# Qwiic_Mux_PCA9846.net
KiCad netlist of a schematic drawn in EAGLE
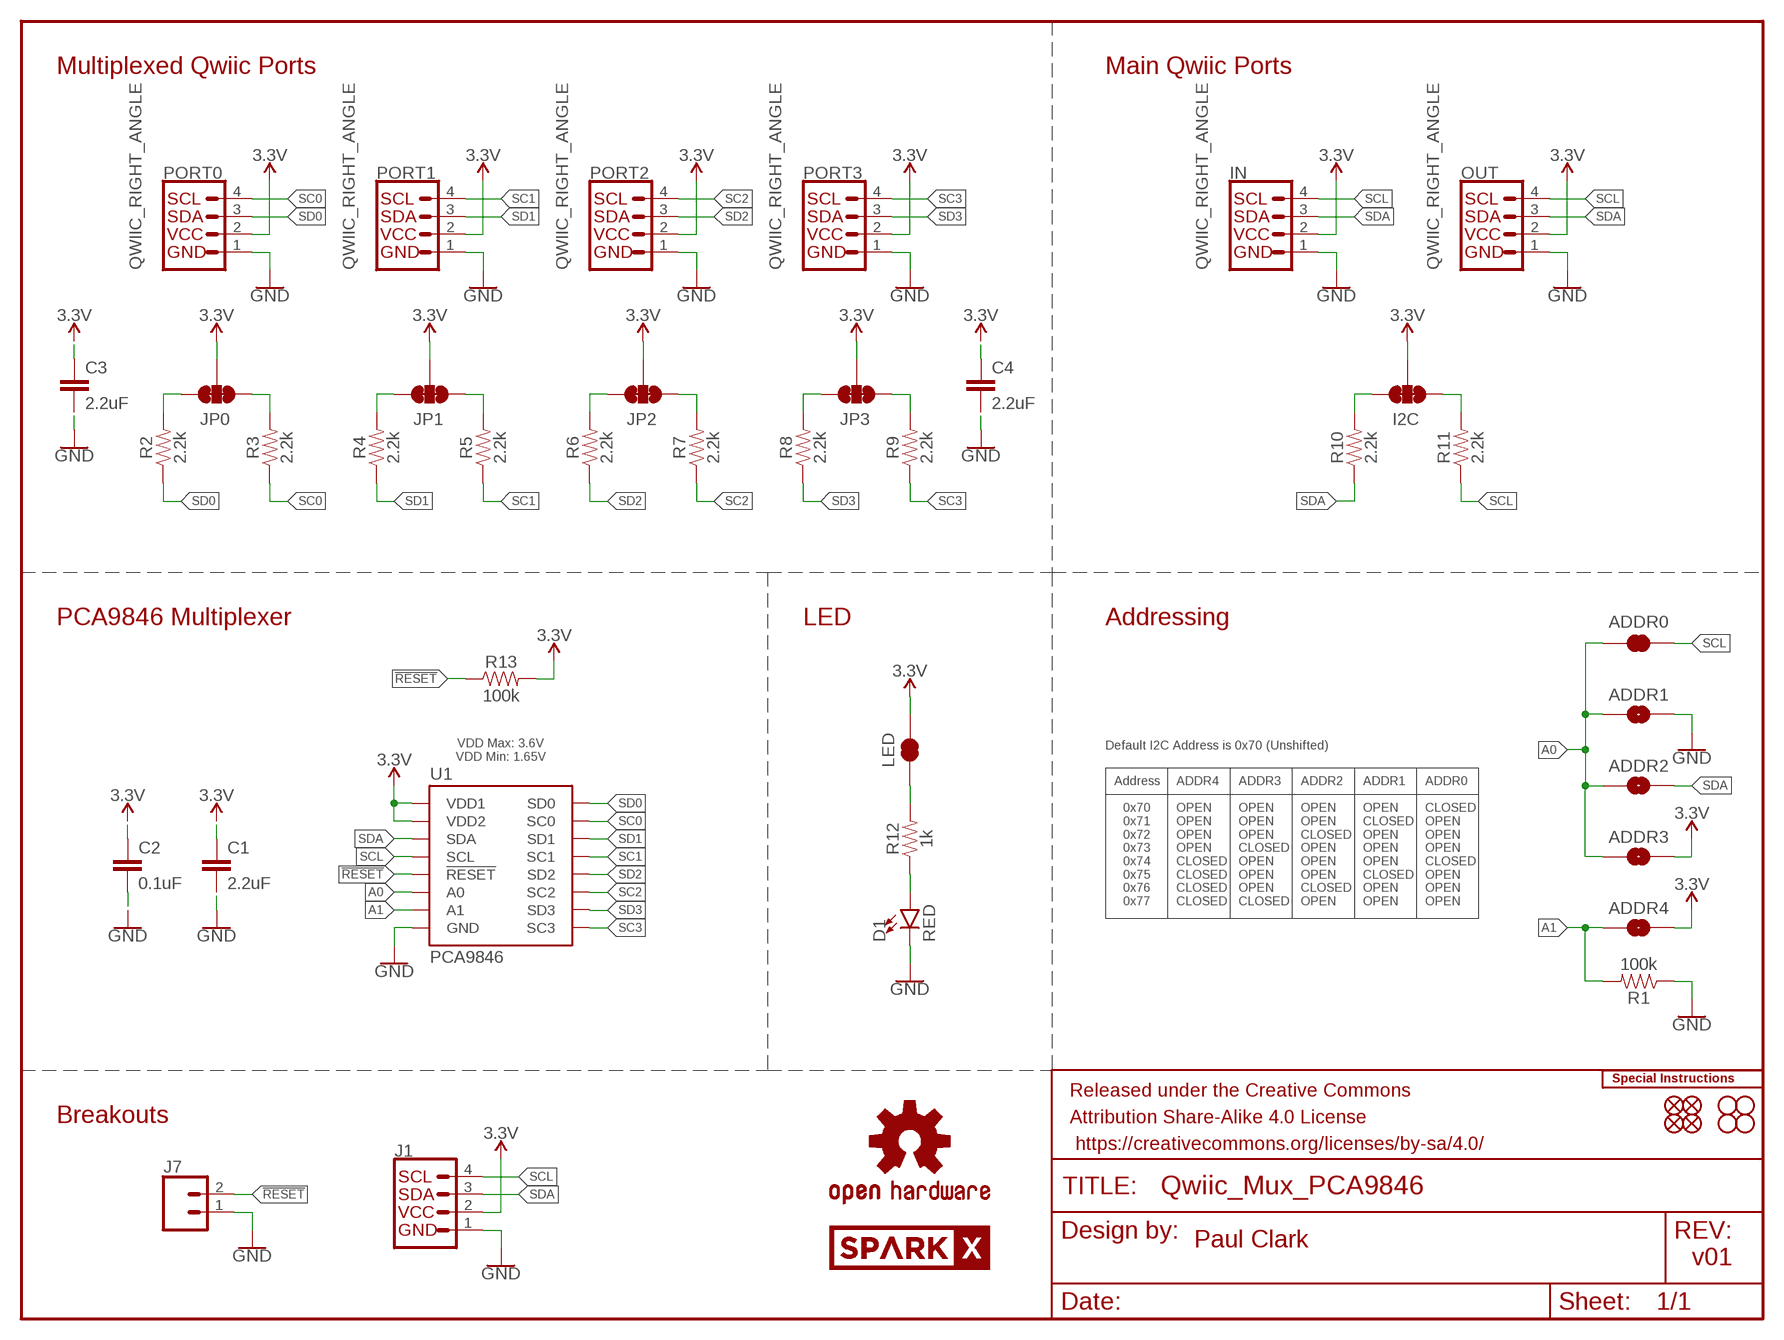
[diagram p0: schematic, sheet 1]

(export (version "E")
  (design (tool "Eeschema 10.0.6"))
  (components
    (comp (ref "ADDR0")
      (value "JUMPER-SMT_2_NC_TRACE_SILK")
      (footprint "eagle-import:SMT-JUMPER_2_NC_TRACE_SILK")
      (libsource (lib "eagle-import") (part "JUMPER-SMT_2_NC_TRACE_SILK"))
    )
    (comp (ref "ADDR1")
      (value "JUMPER-SMT_2_NO_SILK")
      (footprint "eagle-import:SMT-JUMPER_2_NO_SILK")
      (libsource (lib "eagle-import") (part "JUMPER-SMT_2_NO_SILK"))
    )
    (comp (ref "ADDR2")
      (value "JUMPER-SMT_2_NO_SILK")
      (footprint "eagle-import:SMT-JUMPER_2_NO_SILK")
      (libsource (lib "eagle-import") (part "JUMPER-SMT_2_NO_SILK"))
    )
    (comp (ref "ADDR3")
      (value "JUMPER-SMT_2_NO_SILK")
      (footprint "eagle-import:SMT-JUMPER_2_NO_SILK")
      (libsource (lib "eagle-import") (part "JUMPER-SMT_2_NO_SILK"))
    )
    (comp (ref "ADDR4")
      (value "JUMPER-SMT_2_NO_SILK")
      (footprint "eagle-import:SMT-JUMPER_2_NO_SILK")
      (libsource (lib "eagle-import") (part "JUMPER-SMT_2_NO_SILK"))
    )
    (comp (ref "C1")
      (value "2.2uF")
      (footprint "eagle-import:0402-TIGHT")
      (libsource (lib "eagle-import") (part "2.2UF-0402_TIGHT-10V-10%-X5R"))
    )
    (comp (ref "C2")
      (value "0.1uF")
      (footprint "eagle-import:0402-TIGHT")
      (libsource (lib "eagle-import") (part "0.1UF-0402T-6.3V-10%-X7R"))
    )
    (comp (ref "C3")
      (value "2.2uF")
      (footprint "eagle-import:0402-TIGHT")
      (libsource (lib "eagle-import") (part "2.2UF-0402_TIGHT-10V-10%-X5R"))
    )
    (comp (ref "C4")
      (value "2.2uF")
      (footprint "eagle-import:0402-TIGHT")
      (libsource (lib "eagle-import") (part "2.2UF-0402_TIGHT-10V-10%-X5R"))
    )
    (comp (ref "D1")
      (value "RED")
      (footprint "eagle-import:LED-0603")
      (libsource (lib "eagle-import") (part "LED-RED0603"))
    )
    (comp (ref "FD1")
      (value "FIDUCIAL1X2")
      (footprint "eagle-import:FIDUCIAL-1X2")
      (libsource (lib "eagle-import") (part "FIDUCIAL1X2"))
    )
    (comp (ref "FD2")
      (value "FIDUCIAL1X2")
      (footprint "eagle-import:FIDUCIAL-1X2")
      (libsource (lib "eagle-import") (part "FIDUCIAL1X2"))
    )
    (comp (ref "FD3")
      (value "FIDUCIAL1X2")
      (footprint "eagle-import:FIDUCIAL-1X2")
      (libsource (lib "eagle-import") (part "FIDUCIAL1X2"))
    )
    (comp (ref "FD4")
      (value "FIDUCIAL1X2")
      (footprint "eagle-import:FIDUCIAL-1X2")
      (libsource (lib "eagle-import") (part "FIDUCIAL1X2"))
    )
    (comp (ref "FRAME1")
      (value "FRAME-LETTER")
      (footprint "eagle-import:CREATIVE_COMMONS")
      (libsource (lib "eagle-import") (part "FRAME-LETTER"))
    )
    (comp (ref "H1")
      (value "STAND-OFF")
      (footprint "eagle-import:STAND-OFF")
      (libsource (lib "eagle-import") (part "STAND-OFF"))
    )
    (comp (ref "H2")
      (value "STAND-OFF")
      (footprint "eagle-import:STAND-OFF")
      (libsource (lib "eagle-import") (part "STAND-OFF"))
    )
    (comp (ref "H3")
      (value "STAND-OFF")
      (footprint "eagle-import:STAND-OFF")
      (libsource (lib "eagle-import") (part "STAND-OFF"))
    )
    (comp (ref "H4")
      (value "STAND-OFF")
      (footprint "eagle-import:STAND-OFF")
      (libsource (lib "eagle-import") (part "STAND-OFF"))
    )
    (comp (ref "I2C")
      (value "JUMPER-SMT_3_2-NC_TRACE_SILK")
      (footprint "eagle-import:SMT-JUMPER_3_2-NC_TRACE_SILK")
      (libsource (lib "eagle-import") (part "JUMPER-SMT_3_2-NC_TRACE_SILK"))
    )
    (comp (ref "IN")
      (value "QWIIC_RIGHT_ANGLE")
      (footprint "eagle-import:JST04_1MM_RA")
      (libsource (lib "eagle-import") (part "QWIIC_CONNECTORJS-1MM"))
    )
    (comp (ref "J1")
      (value "I2C_STANDARD_NO_SILK")
      (footprint "eagle-import:1X04_NO_SILK")
      (libsource (lib "eagle-import") (part "I2C_STANDARD_NO_SILK"))
    )
    (comp (ref "J7")
      (value "CONN_021X02_NO_SILK")
      (footprint "eagle-import:1X02_NO_SILK")
      (libsource (lib "eagle-import") (part "CONN_021X02_NO_SILK"))
    )
    (comp (ref "JP0")
      (value "JUMPER-SMT_3_2-NC_TRACE_SILK")
      (footprint "eagle-import:SMT-JUMPER_3_2-NC_TRACE_SILK")
      (libsource (lib "eagle-import") (part "JUMPER-SMT_3_2-NC_TRACE_SILK"))
    )
    (comp (ref "JP1")
      (value "JUMPER-SMT_3_2-NC_TRACE_SILK")
      (footprint "eagle-import:SMT-JUMPER_3_2-NC_TRACE_SILK")
      (libsource (lib "eagle-import") (part "JUMPER-SMT_3_2-NC_TRACE_SILK"))
    )
    (comp (ref "JP2")
      (value "JUMPER-SMT_3_2-NC_TRACE_SILK")
      (footprint "eagle-import:SMT-JUMPER_3_2-NC_TRACE_SILK")
      (libsource (lib "eagle-import") (part "JUMPER-SMT_3_2-NC_TRACE_SILK"))
    )
    (comp (ref "JP3")
      (value "JUMPER-SMT_3_2-NC_TRACE_SILK")
      (footprint "eagle-import:SMT-JUMPER_3_2-NC_TRACE_SILK")
      (libsource (lib "eagle-import") (part "JUMPER-SMT_3_2-NC_TRACE_SILK"))
    )
    (comp (ref "LED")
      (value "JUMPER-SMT_2_NC_TRACE_SILK")
      (footprint "eagle-import:SMT-JUMPER_2_NC_TRACE_SILK")
      (libsource (lib "eagle-import") (part "JUMPER-SMT_2_NC_TRACE_SILK"))
    )
    (comp (ref "LOGO1")
      (value "SPECIAL_INSTRUCTIONS-ORDERING")
      (footprint "eagle-import:ORDERING_INSTRUCTIONS")
      (libsource (lib "eagle-import") (part "SPECIAL_INSTRUCTIONS-ORDERING"))
    )
    (comp (ref "LOGO4")
      (value "OSHW-LOGOMINI")
      (footprint "eagle-import:OSHW-LOGO-MINI")
      (libsource (lib "eagle-import") (part "OSHW-LOGOMINI"))
    )
    (comp (ref "OUT")
      (value "QWIIC_RIGHT_ANGLE")
      (footprint "eagle-import:JST04_1MM_RA")
      (libsource (lib "eagle-import") (part "QWIIC_CONNECTORJS-1MM"))
    )
    (comp (ref "PORT0")
      (value "QWIIC_RIGHT_ANGLE")
      (footprint "eagle-import:JST04_1MM_RA")
      (libsource (lib "eagle-import") (part "QWIIC_CONNECTORJS-1MM"))
    )
    (comp (ref "PORT1")
      (value "QWIIC_RIGHT_ANGLE")
      (footprint "eagle-import:JST04_1MM_RA")
      (libsource (lib "eagle-import") (part "QWIIC_CONNECTORJS-1MM"))
    )
    (comp (ref "PORT2")
      (value "QWIIC_RIGHT_ANGLE")
      (footprint "eagle-import:JST04_1MM_RA")
      (libsource (lib "eagle-import") (part "QWIIC_CONNECTORJS-1MM"))
    )
    (comp (ref "PORT3")
      (value "QWIIC_RIGHT_ANGLE")
      (footprint "eagle-import:JST04_1MM_RA")
      (libsource (lib "eagle-import") (part "QWIIC_CONNECTORJS-1MM"))
    )
    (comp (ref "R1")
      (value "100k")
      (footprint "eagle-import:0402-TIGHT")
      (libsource (lib "eagle-import") (part "100KOHM-0402T-1/16W-1%"))
    )
    (comp (ref "R2")
      (value "2.2k")
      (footprint "eagle-import:0402-TIGHT")
      (libsource (lib "eagle-import") (part "2.2KOHM-0402T-1/16W-1%"))
    )
    (comp (ref "R3")
      (value "2.2k")
      (footprint "eagle-import:0402-TIGHT")
      (libsource (lib "eagle-import") (part "2.2KOHM-0402T-1/16W-1%"))
    )
    (comp (ref "R4")
      (value "2.2k")
      (footprint "eagle-import:0402-TIGHT")
      (libsource (lib "eagle-import") (part "2.2KOHM-0402T-1/16W-1%"))
    )
    (comp (ref "R5")
      (value "2.2k")
      (footprint "eagle-import:0402-TIGHT")
      (libsource (lib "eagle-import") (part "2.2KOHM-0402T-1/16W-1%"))
    )
    (comp (ref "R6")
      (value "2.2k")
      (footprint "eagle-import:0402-TIGHT")
      (libsource (lib "eagle-import") (part "2.2KOHM-0402T-1/16W-1%"))
    )
    (comp (ref "R7")
      (value "2.2k")
      (footprint "eagle-import:0402-TIGHT")
      (libsource (lib "eagle-import") (part "2.2KOHM-0402T-1/16W-1%"))
    )
    (comp (ref "R8")
      (value "2.2k")
      (footprint "eagle-import:0402-TIGHT")
      (libsource (lib "eagle-import") (part "2.2KOHM-0402T-1/16W-1%"))
    )
    (comp (ref "R9")
      (value "2.2k")
      (footprint "eagle-import:0402-TIGHT")
      (libsource (lib "eagle-import") (part "2.2KOHM-0402T-1/16W-1%"))
    )
    (comp (ref "R10")
      (value "2.2k")
      (footprint "eagle-import:0402-TIGHT")
      (libsource (lib "eagle-import") (part "2.2KOHM-0402T-1/16W-1%"))
    )
    (comp (ref "R11")
      (value "2.2k")
      (footprint "eagle-import:0402-TIGHT")
      (libsource (lib "eagle-import") (part "2.2KOHM-0402T-1/16W-1%"))
    )
    (comp (ref "R12")
      (value "1k")
      (footprint "eagle-import:0402-TIGHT")
      (libsource (lib "eagle-import") (part "1KOHM-0402T-1/16W-1%"))
    )
    (comp (ref "R13")
      (value "100k")
      (footprint "eagle-import:0402-TIGHT")
      (libsource (lib "eagle-import") (part "100KOHM-0402T-1/16W-1%"))
    )
    (comp (ref "U$1")
      (value "SPARKX-LOGO3")
      (footprint "eagle-import:SPARKX-SMALL")
      (libsource (lib "eagle-import") (part "SPARKX-LOGO3"))
    )
    (comp (ref "U1")
      (value "PCA9846")
      (footprint "eagle-import:SOT403-1")
      (libsource (lib "eagle-import") (part "PCA9846"))
    )
  )
  (nets
    (net (code "1") (name "/~{RESET}") (class "Default")
      (node (ref "J7") (pin "2") (pinfunction "2_2") (pintype "passive"))
      (node (ref "R13") (pin "1") (pinfunction "1_1") (pintype "passive"))
      (node (ref "U1") (pin "3") (pinfunction "~{RESET}_3") (pintype "input"))
    )
    (net (code "2") (name "3.3V") (class "Default")
      (node (ref "ADDR3") (pin "2") (pinfunction "2_2") (pintype "passive"))
      (node (ref "ADDR4") (pin "2") (pinfunction "2_2") (pintype "passive"))
      (node (ref "C1") (pin "1") (pinfunction "1_1") (pintype "passive"))
      (node (ref "C2") (pin "1") (pinfunction "1_1") (pintype "passive"))
      (node (ref "C3") (pin "1") (pinfunction "1_1") (pintype "passive"))
      (node (ref "C4") (pin "1") (pinfunction "1_1") (pintype "passive"))
      (node (ref "I2C") (pin "2") (pinfunction "2_2") (pintype "passive"))
      (node (ref "IN") (pin "2") (pinfunction "2_2") (pintype "power_in"))
      (node (ref "J1") (pin "2") (pinfunction "2_2") (pintype "power_in"))
      (node (ref "JP0") (pin "2") (pinfunction "2_2") (pintype "passive"))
      (node (ref "JP1") (pin "2") (pinfunction "2_2") (pintype "passive"))
      (node (ref "JP2") (pin "2") (pinfunction "2_2") (pintype "passive"))
      (node (ref "JP3") (pin "2") (pinfunction "2_2") (pintype "passive"))
      (node (ref "LED") (pin "2") (pinfunction "2_2") (pintype "passive"))
      (node (ref "OUT") (pin "2") (pinfunction "2_2") (pintype "power_in"))
      (node (ref "PORT0") (pin "2") (pinfunction "2_2") (pintype "power_in"))
      (node (ref "PORT1") (pin "2") (pinfunction "2_2") (pintype "power_in"))
      (node (ref "PORT2") (pin "2") (pinfunction "2_2") (pintype "power_in"))
      (node (ref "PORT3") (pin "2") (pinfunction "2_2") (pintype "power_in"))
      (node (ref "R13") (pin "2") (pinfunction "2_2") (pintype "passive"))
      (node (ref "U1") (pin "1") (pinfunction "VDD1_1") (pintype "power_in"))
      (node (ref "U1") (pin "16") (pinfunction "VDD2_16") (pintype "power_in"))
    )
    (net (code "3") (name "A0") (class "Default")
      (node (ref "ADDR0") (pin "1") (pinfunction "1_1") (pintype "passive"))
      (node (ref "ADDR1") (pin "1") (pinfunction "1_1") (pintype "passive"))
      (node (ref "ADDR2") (pin "1") (pinfunction "1_1") (pintype "passive"))
      (node (ref "ADDR3") (pin "1") (pinfunction "1_1") (pintype "passive"))
      (node (ref "U1") (pin "2") (pinfunction "A0_2") (pintype "bidirectional"))
    )
    (net (code "4") (name "A1") (class "Default")
      (node (ref "ADDR4") (pin "1") (pinfunction "1_1") (pintype "passive"))
      (node (ref "R1") (pin "2") (pinfunction "2_2") (pintype "passive"))
      (node (ref "U1") (pin "13") (pinfunction "A1_13") (pintype "bidirectional"))
    )
    (net (code "5") (name "GND") (class "Default")
      (node (ref "ADDR1") (pin "2") (pinfunction "2_2") (pintype "passive"))
      (node (ref "C1") (pin "2") (pinfunction "2_2") (pintype "passive"))
      (node (ref "C2") (pin "2") (pinfunction "2_2") (pintype "passive"))
      (node (ref "C3") (pin "2") (pinfunction "2_2") (pintype "passive"))
      (node (ref "C4") (pin "2") (pinfunction "2_2") (pintype "passive"))
      (node (ref "D1") (pin "C") (pinfunction "C_C") (pintype "passive"))
      (node (ref "IN") (pin "1") (pinfunction "1_1") (pintype "power_in"))
      (node (ref "J1") (pin "1") (pinfunction "1_1") (pintype "power_in"))
      (node (ref "J7") (pin "1") (pinfunction "1_1") (pintype "passive"))
      (node (ref "OUT") (pin "1") (pinfunction "1_1") (pintype "power_in"))
      (node (ref "PORT0") (pin "1") (pinfunction "1_1") (pintype "power_in"))
      (node (ref "PORT1") (pin "1") (pinfunction "1_1") (pintype "power_in"))
      (node (ref "PORT2") (pin "1") (pinfunction "1_1") (pintype "power_in"))
      (node (ref "PORT3") (pin "1") (pinfunction "1_1") (pintype "power_in"))
      (node (ref "R1") (pin "1") (pinfunction "1_1") (pintype "passive"))
      (node (ref "U1") (pin "8") (pinfunction "GND_8") (pintype "power_in"))
    )
    (net (code "6") (name "Net-(D1-PadA)") (class "Default")
      (node (ref "D1") (pin "A") (pinfunction "A_A") (pintype "passive"))
      (node (ref "R12") (pin "1") (pinfunction "1_1") (pintype "passive"))
    )
    (net (code "7") (name "Net-(I2C-Pad1)") (class "Default")
      (node (ref "I2C") (pin "1") (pinfunction "1_1") (pintype "passive"))
      (node (ref "R11") (pin "2") (pinfunction "2_2") (pintype "passive"))
    )
    (net (code "8") (name "Net-(I2C-Pad3)") (class "Default")
      (node (ref "I2C") (pin "3") (pinfunction "3_3") (pintype "passive"))
      (node (ref "R10") (pin "2") (pinfunction "2_2") (pintype "passive"))
    )
    (net (code "9") (name "Net-(JP0-Pad1)") (class "Default")
      (node (ref "JP0") (pin "1") (pinfunction "1_1") (pintype "passive"))
      (node (ref "R3") (pin "2") (pinfunction "2_2") (pintype "passive"))
    )
    (net (code "10") (name "Net-(JP0-Pad3)") (class "Default")
      (node (ref "JP0") (pin "3") (pinfunction "3_3") (pintype "passive"))
      (node (ref "R2") (pin "2") (pinfunction "2_2") (pintype "passive"))
    )
    (net (code "11") (name "Net-(JP1-Pad1)") (class "Default")
      (node (ref "JP1") (pin "1") (pinfunction "1_1") (pintype "passive"))
      (node (ref "R5") (pin "2") (pinfunction "2_2") (pintype "passive"))
    )
    (net (code "12") (name "Net-(JP1-Pad3)") (class "Default")
      (node (ref "JP1") (pin "3") (pinfunction "3_3") (pintype "passive"))
      (node (ref "R4") (pin "2") (pinfunction "2_2") (pintype "passive"))
    )
    (net (code "13") (name "Net-(JP2-Pad1)") (class "Default")
      (node (ref "JP2") (pin "1") (pinfunction "1_1") (pintype "passive"))
      (node (ref "R7") (pin "2") (pinfunction "2_2") (pintype "passive"))
    )
    (net (code "14") (name "Net-(JP2-Pad3)") (class "Default")
      (node (ref "JP2") (pin "3") (pinfunction "3_3") (pintype "passive"))
      (node (ref "R6") (pin "2") (pinfunction "2_2") (pintype "passive"))
    )
    (net (code "15") (name "Net-(JP3-Pad1)") (class "Default")
      (node (ref "JP3") (pin "1") (pinfunction "1_1") (pintype "passive"))
      (node (ref "R9") (pin "2") (pinfunction "2_2") (pintype "passive"))
    )
    (net (code "16") (name "Net-(JP3-Pad3)") (class "Default")
      (node (ref "JP3") (pin "3") (pinfunction "3_3") (pintype "passive"))
      (node (ref "R8") (pin "2") (pinfunction "2_2") (pintype "passive"))
    )
    (net (code "17") (name "Net-(LED-Pad1)") (class "Default")
      (node (ref "LED") (pin "1") (pinfunction "1_1") (pintype "passive"))
      (node (ref "R12") (pin "2") (pinfunction "2_2") (pintype "passive"))
    )
    (net (code "18") (name "SC0") (class "Default")
      (node (ref "PORT0") (pin "4") (pinfunction "4_4") (pintype "passive"))
      (node (ref "R3") (pin "1") (pinfunction "1_1") (pintype "passive"))
      (node (ref "U1") (pin "5") (pinfunction "SC0_5") (pintype "bidirectional"))
    )
    (net (code "19") (name "SC1") (class "Default")
      (node (ref "PORT1") (pin "4") (pinfunction "4_4") (pintype "passive"))
      (node (ref "R5") (pin "1") (pinfunction "1_1") (pintype "passive"))
      (node (ref "U1") (pin "7") (pinfunction "SC1_7") (pintype "bidirectional"))
    )
    (net (code "20") (name "SC2") (class "Default")
      (node (ref "PORT2") (pin "4") (pinfunction "4_4") (pintype "passive"))
      (node (ref "R7") (pin "1") (pinfunction "1_1") (pintype "passive"))
      (node (ref "U1") (pin "10") (pinfunction "SC2_10") (pintype "bidirectional"))
    )
    (net (code "21") (name "SC3") (class "Default")
      (node (ref "PORT3") (pin "4") (pinfunction "4_4") (pintype "passive"))
      (node (ref "R9") (pin "1") (pinfunction "1_1") (pintype "passive"))
      (node (ref "U1") (pin "12") (pinfunction "SC3_12") (pintype "bidirectional"))
    )
    (net (code "22") (name "SCL") (class "Default")
      (node (ref "ADDR0") (pin "2") (pinfunction "2_2") (pintype "passive"))
      (node (ref "IN") (pin "4") (pinfunction "4_4") (pintype "passive"))
      (node (ref "J1") (pin "4") (pinfunction "4_4") (pintype "passive"))
      (node (ref "OUT") (pin "4") (pinfunction "4_4") (pintype "passive"))
      (node (ref "R11") (pin "1") (pinfunction "1_1") (pintype "passive"))
      (node (ref "U1") (pin "14") (pinfunction "SCL_14") (pintype "bidirectional"))
    )
    (net (code "23") (name "SD0") (class "Default")
      (node (ref "PORT0") (pin "3") (pinfunction "3_3") (pintype "passive"))
      (node (ref "R2") (pin "1") (pinfunction "1_1") (pintype "passive"))
      (node (ref "U1") (pin "4") (pinfunction "SD0_4") (pintype "bidirectional"))
    )
    (net (code "24") (name "SD1") (class "Default")
      (node (ref "PORT1") (pin "3") (pinfunction "3_3") (pintype "passive"))
      (node (ref "R4") (pin "1") (pinfunction "1_1") (pintype "passive"))
      (node (ref "U1") (pin "6") (pinfunction "SD1_6") (pintype "bidirectional"))
    )
    (net (code "25") (name "SD2") (class "Default")
      (node (ref "PORT2") (pin "3") (pinfunction "3_3") (pintype "passive"))
      (node (ref "R6") (pin "1") (pinfunction "1_1") (pintype "passive"))
      (node (ref "U1") (pin "9") (pinfunction "SD2_9") (pintype "bidirectional"))
    )
    (net (code "26") (name "SD3") (class "Default")
      (node (ref "PORT3") (pin "3") (pinfunction "3_3") (pintype "passive"))
      (node (ref "R8") (pin "1") (pinfunction "1_1") (pintype "passive"))
      (node (ref "U1") (pin "11") (pinfunction "SD3_11") (pintype "bidirectional"))
    )
    (net (code "27") (name "SDA") (class "Default")
      (node (ref "ADDR2") (pin "2") (pinfunction "2_2") (pintype "passive"))
      (node (ref "IN") (pin "3") (pinfunction "3_3") (pintype "passive"))
      (node (ref "J1") (pin "3") (pinfunction "3_3") (pintype "passive"))
      (node (ref "OUT") (pin "3") (pinfunction "3_3") (pintype "passive"))
      (node (ref "R10") (pin "1") (pinfunction "1_1") (pintype "passive"))
      (node (ref "U1") (pin "15") (pinfunction "SDA_15") (pintype "bidirectional"))
    )
  )
)
